# DP_Slave_Sch.net
KiCad netlist of a schematic drawn in Altium Designer
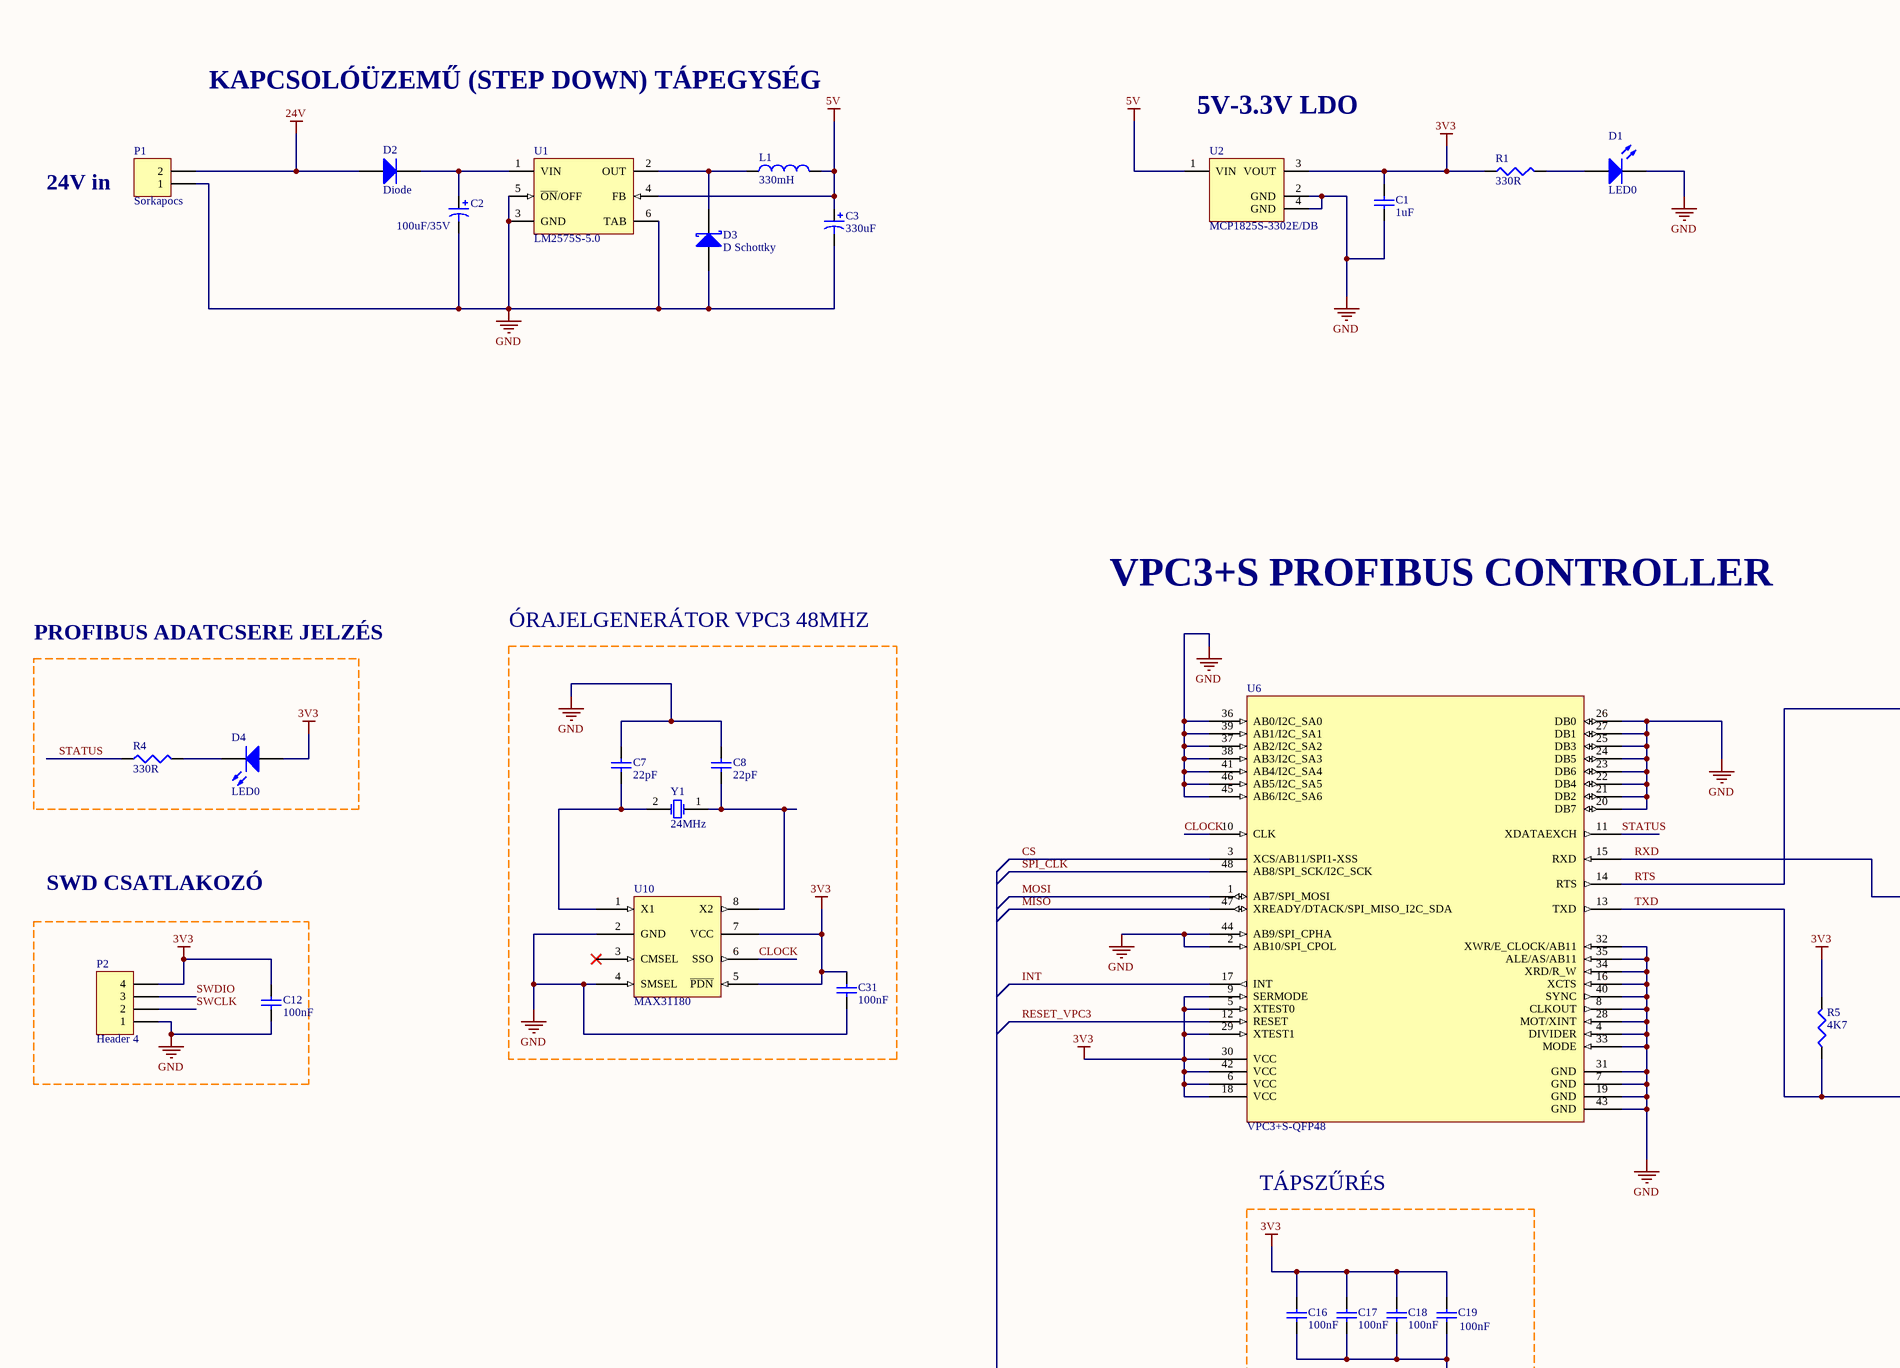
[diagram p0: DP_Slave_Sch.SchDoc, top left]
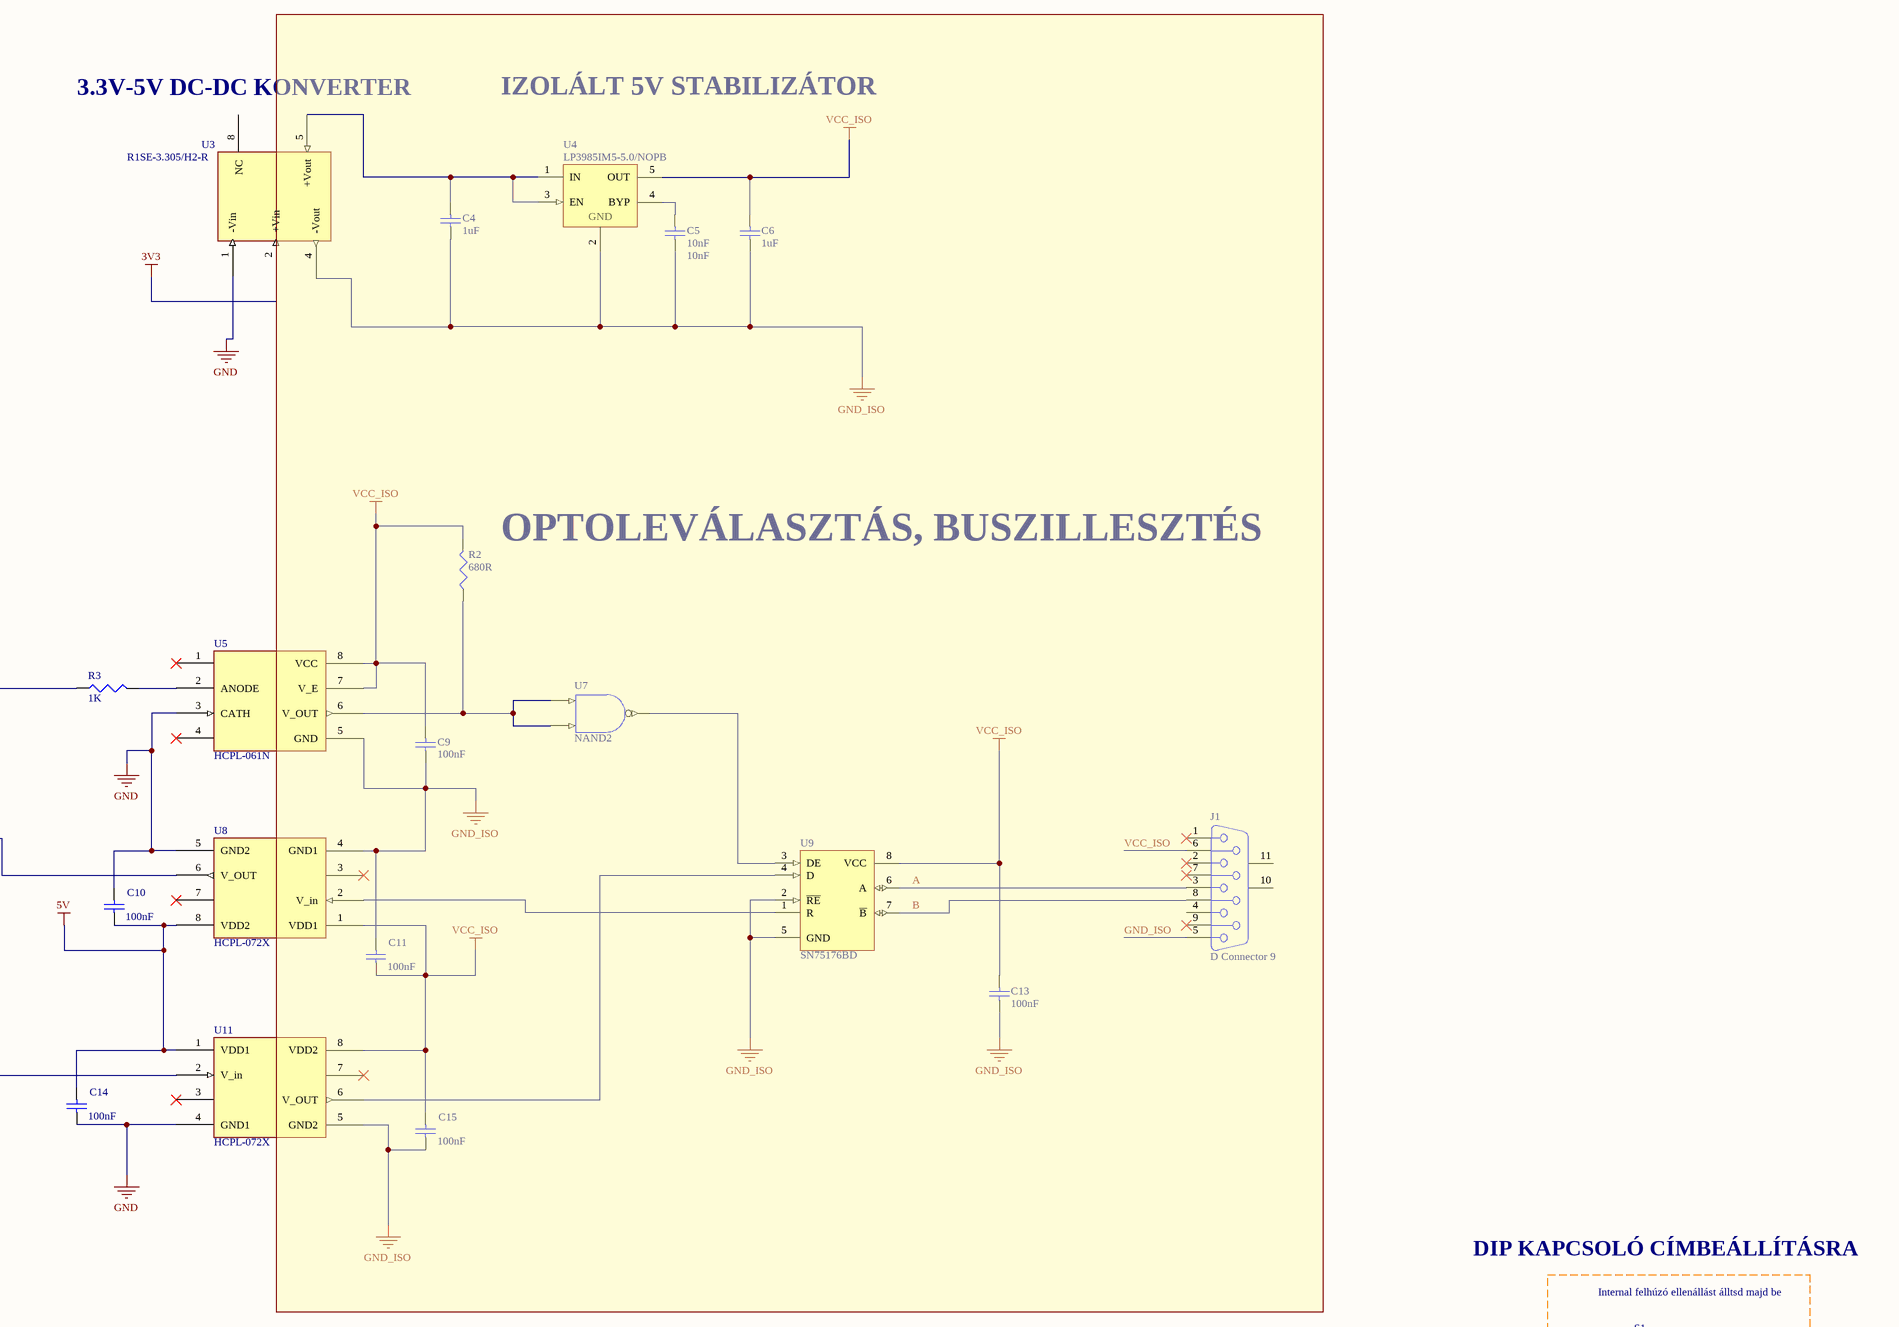
[diagram p1: DP_Slave_Sch.SchDoc, top right]
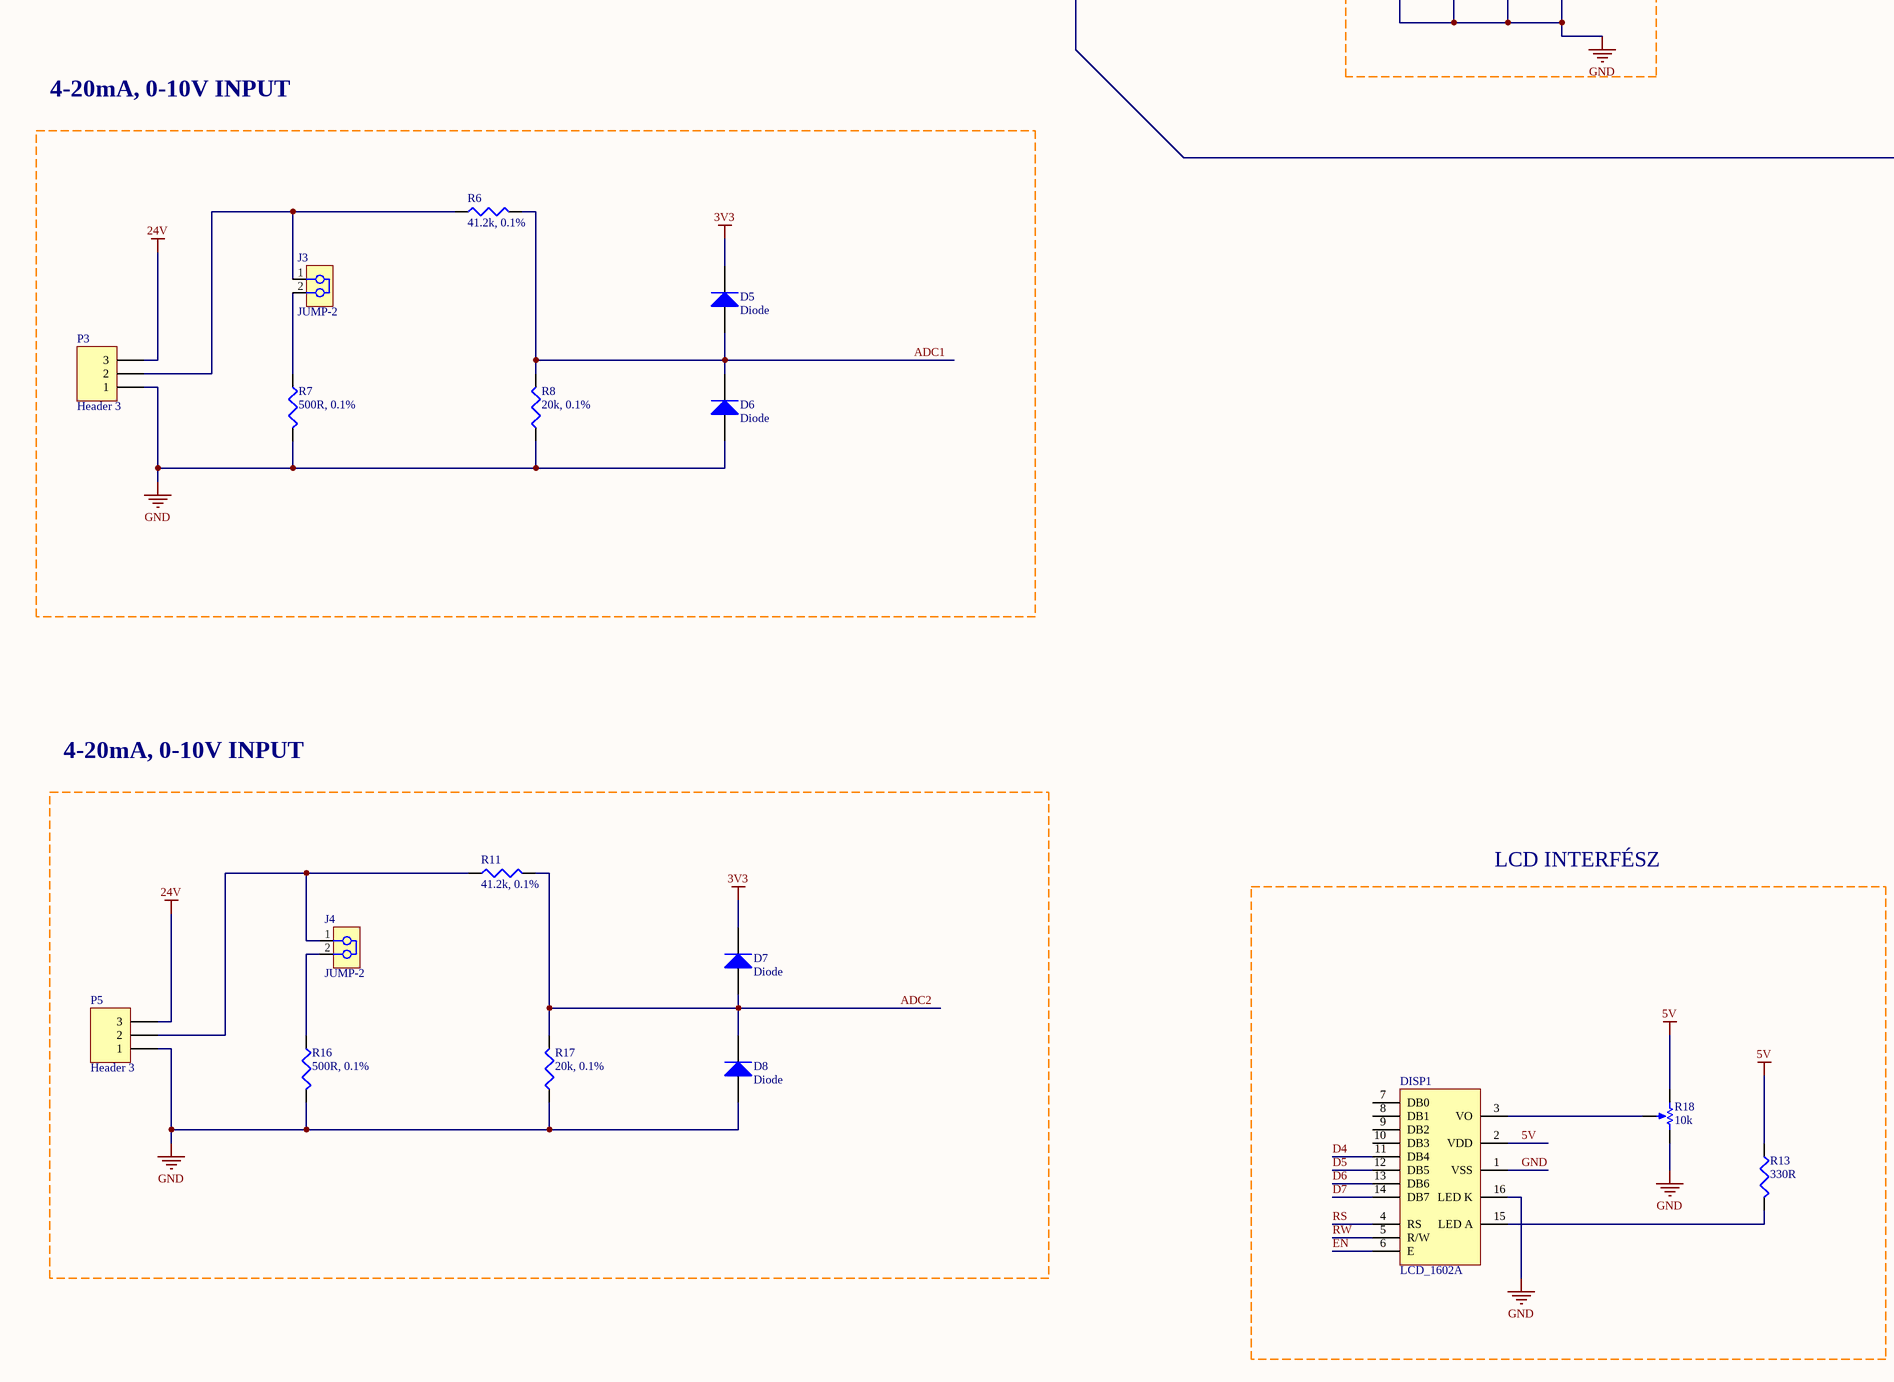
[diagram p2: DP_Slave_Sch.SchDoc, bottom left]
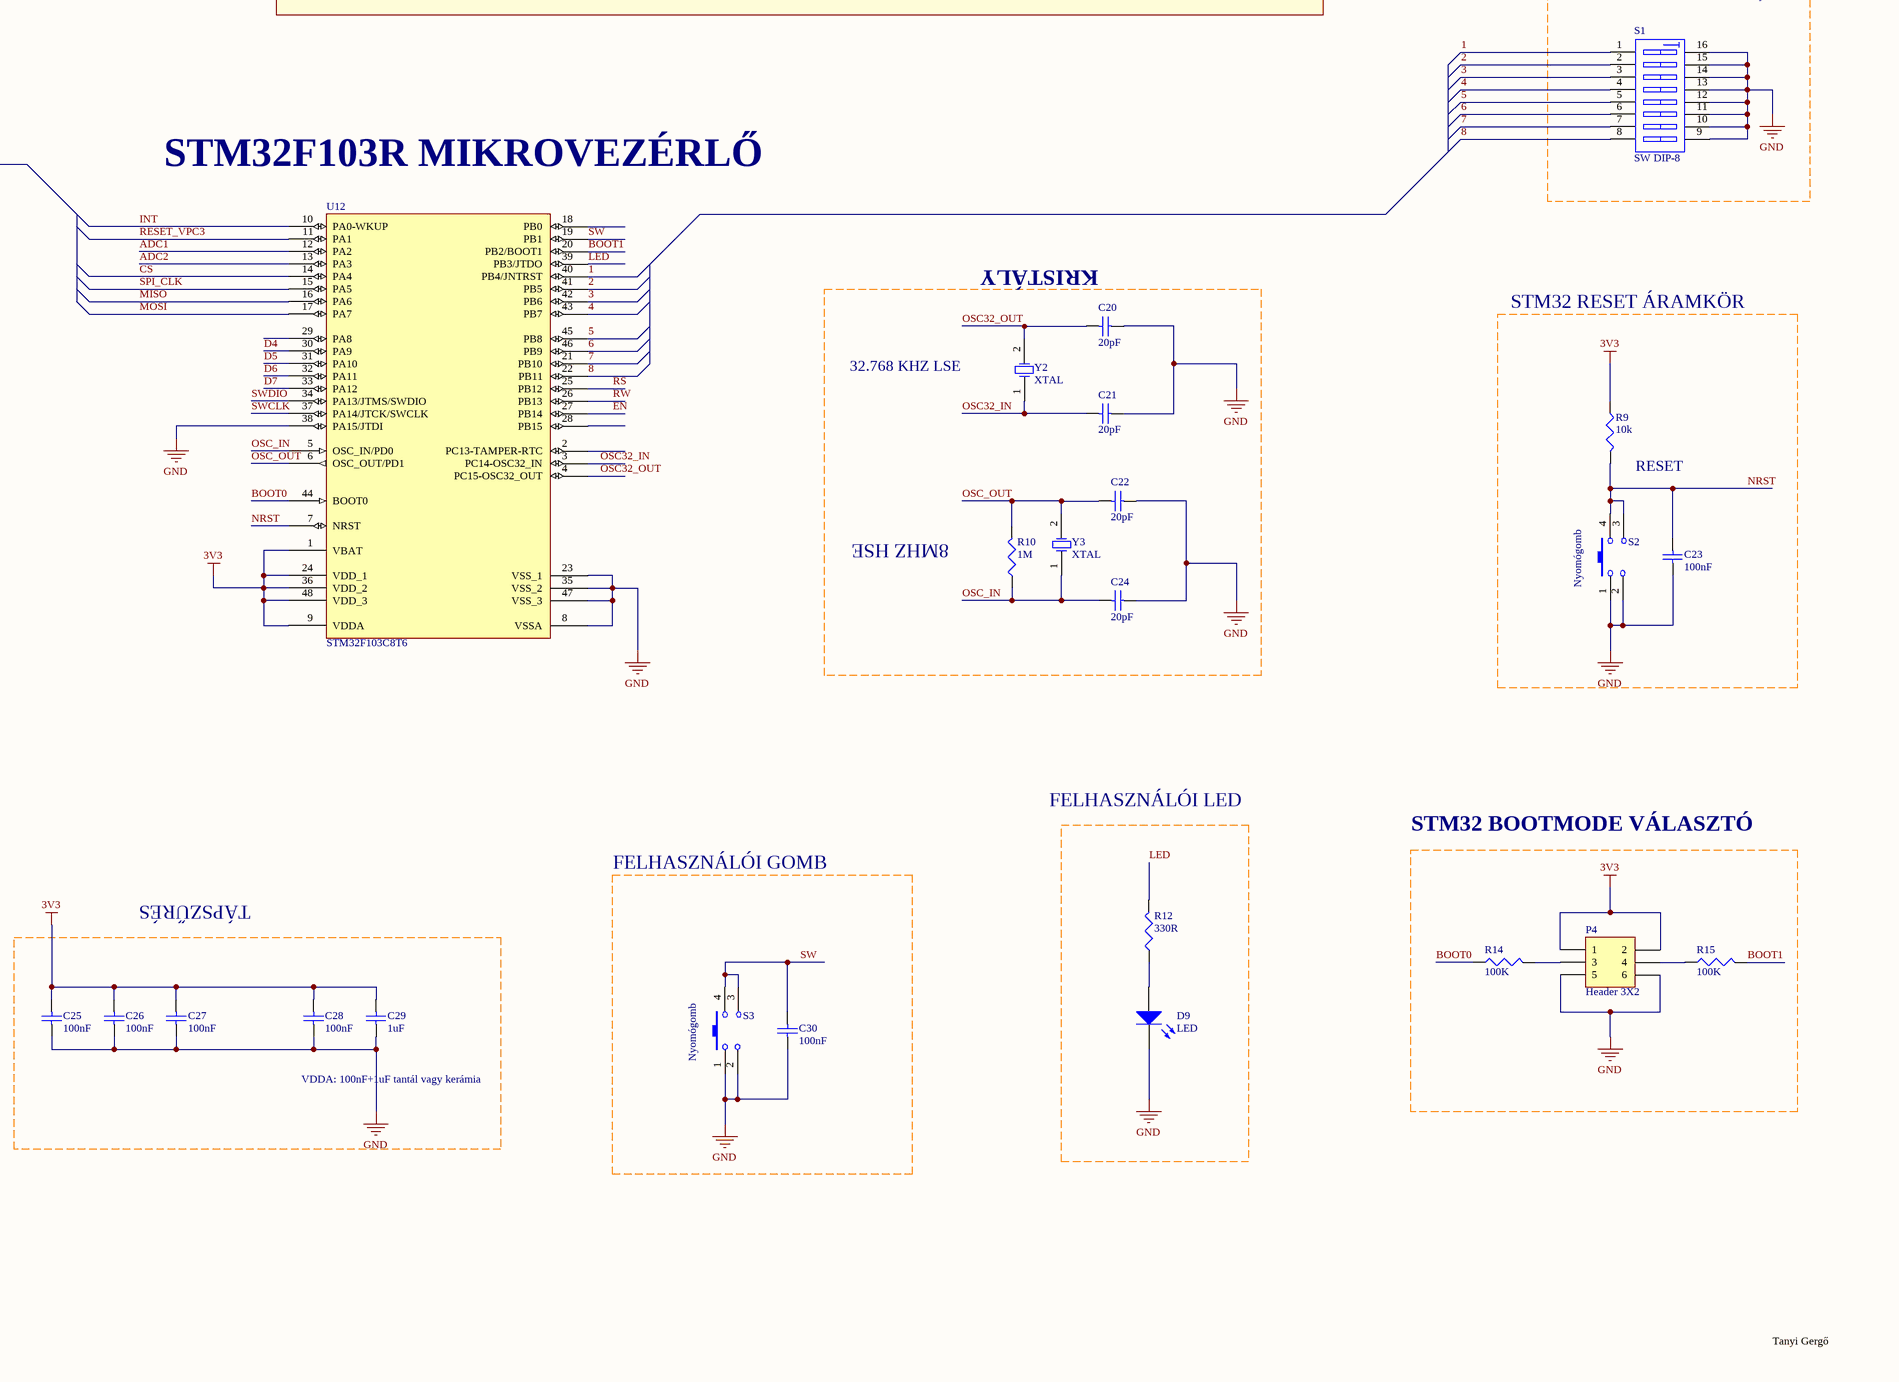
[diagram p3: DP_Slave_Sch.SchDoc, bottom right]

(export (version "E")
  (design (tool "Eeschema 10.0.6"))
  (components
    (comp (ref "C1")
      (value "1uF")
      (footprint "C1206")
      (description "Szűrőkondi")
      (fields (field (name "PUBLISHER") "Altium Limited"))
      (libsource (lib "Miscellaneous Devices") (part "Cap Semi"))
    )
    (comp (ref "C2")
      (value "100uF/35V")
      (footprint "MyFootprints:SMD Elkó")
      (description "SMD elkó/40V")
      (fields (field (name "PUBLISHER") "Altium Limited"))
      (libsource (lib "Miscellaneous Devices") (part "Cap Pol3"))
    )
    (comp (ref "C3")
      (value "330uF")
      (footprint "MyFootprints:SMD Elkó")
      (description "LDO kimeneti polárkondi")
      (fields (field (name "PUBLISHER") "Altium Limited"))
      (libsource (lib "Miscellaneous Devices") (part "Cap Pol3"))
    )
    (comp (ref "C4")
      (value "1uF")
      (footprint "C1206")
      (description "Capacitor (Semiconductor SIM Model)")
      (fields (field (name "PUBLISHER") "Altium Limited"))
      (libsource (lib "Miscellaneous Devices") (part "Cap Semi"))
    )
    (comp (ref "C5")
      (value "10nF")
      (footprint "C1206")
      (description "Capacitor (Semiconductor SIM Model)")
      (fields (field (name "ALTIUM_VALUE") "10nF") (field (name "PUBLISHER") "Altium Limited"))
      (libsource (lib "Miscellaneous Devices") (part "Cap Semi"))
    )
    (comp (ref "C6")
      (value "1uF")
      (footprint "C1206")
      (description "Capacitor (Semiconductor SIM Model)")
      (fields (field (name "PUBLISHER") "Altium Limited"))
      (libsource (lib "Miscellaneous Devices") (part "Cap Semi"))
    )
    (comp (ref "C7")
      (value "22pF")
      (footprint "C1206")
      (description "SMD kerámia")
      (fields (field (name "PUBLISHER") "Altium Limited"))
      (libsource (lib "Miscellaneous Devices") (part "Cap Semi"))
    )
    (comp (ref "C8")
      (value "22pF")
      (footprint "C1206")
      (description "SMD kerámia")
      (fields (field (name "PUBLISHER") "Altium Limited"))
      (libsource (lib "Miscellaneous Devices") (part "Cap Semi"))
    )
    (comp (ref "C9")
      (value "100nF")
      (footprint "C1206")
      (description "SMD KERÁMIA")
      (fields (field (name "PUBLISHER") "Altium Limited"))
      (libsource (lib "Miscellaneous Devices") (part "Cap Semi"))
    )
    (comp (ref "C10")
      (value "100nF")
      (footprint "C1206")
      (description "SMD KERÁMIA")
      (fields (field (name "PUBLISHER") "Altium Limited"))
      (libsource (lib "Miscellaneous Devices") (part "Cap Semi"))
    )
    (comp (ref "C11")
      (value "100nF")
      (footprint "C1206")
      (description "SMD KERÁMIA")
      (fields (field (name "PUBLISHER") "Altium Limited"))
      (libsource (lib "Miscellaneous Devices") (part "Cap Semi"))
    )
    (comp (ref "C12")
      (value "100nF")
      (footprint "C1206")
      (description "Szűrőkondi")
      (fields (field (name "PUBLISHER") "Altium Limited"))
      (libsource (lib "Miscellaneous Devices") (part "Cap Semi"))
    )
    (comp (ref "C13")
      (value "100nF")
      (footprint "C1206")
      (description "SMD KERÁMIA")
      (fields (field (name "PUBLISHER") "Altium Limited"))
      (libsource (lib "Miscellaneous Devices") (part "Cap Semi"))
    )
    (comp (ref "C14")
      (value "100nF")
      (footprint "C1206")
      (description "SMD KERÁMIA")
      (fields (field (name "PUBLISHER") "Altium Limited"))
      (libsource (lib "Miscellaneous Devices") (part "Cap Semi"))
    )
    (comp (ref "C15")
      (value "100nF")
      (footprint "C1206")
      (description "SMD KERÁMIA")
      (fields (field (name "PUBLISHER") "Altium Limited"))
      (libsource (lib "Miscellaneous Devices") (part "Cap Semi"))
    )
    (comp (ref "C16")
      (value "100nF")
      (footprint "C1206")
      (description "Capacitor (Semiconductor SIM Model)")
      (fields (field (name "PUBLISHER") "Altium Limited"))
      (libsource (lib "Miscellaneous Devices") (part "Cap Semi"))
    )
    (comp (ref "C17")
      (value "100nF")
      (footprint "C1206")
      (description "Capacitor (Semiconductor SIM Model)")
      (fields (field (name "PUBLISHER") "Altium Limited"))
      (libsource (lib "Miscellaneous Devices") (part "Cap Semi"))
    )
    (comp (ref "C18")
      (value "100nF")
      (footprint "C1206")
      (description "Capacitor (Semiconductor SIM Model)")
      (fields (field (name "PUBLISHER") "Altium Limited"))
      (libsource (lib "Miscellaneous Devices") (part "Cap Semi"))
    )
    (comp (ref "C19")
      (value "100nF")
      (footprint "C1206")
      (description "Capacitor (Semiconductor SIM Model)")
      (fields (field (name "PUBLISHER") "Altium Limited"))
      (libsource (lib "Miscellaneous Devices") (part "Cap Semi"))
    )
    (comp (ref "C20")
      (value "20pF")
      (footprint "C1206")
      (description "SMD kerámia")
      (fields (field (name "PUBLISHER") "Altium Limited"))
      (libsource (lib "Miscellaneous Devices") (part "Cap Semi"))
    )
    (comp (ref "C21")
      (value "20pF")
      (footprint "C1206")
      (description "SMD kerámia")
      (fields (field (name "PUBLISHER") "Altium Limited"))
      (libsource (lib "Miscellaneous Devices") (part "Cap Semi"))
    )
    (comp (ref "C22")
      (value "20pF")
      (footprint "C1206")
      (description "SMD kerámia")
      (fields (field (name "PUBLISHER") "Altium Limited"))
      (libsource (lib "Miscellaneous Devices") (part "Cap Semi"))
    )
    (comp (ref "C23")
      (value "100nF")
      (footprint "C1206")
      (description "Szűrőkondi")
      (fields (field (name "PUBLISHER") "Altium Limited"))
      (libsource (lib "Miscellaneous Devices") (part "Cap Semi"))
    )
    (comp (ref "C24")
      (value "20pF")
      (footprint "C1206")
      (description "SMD kerámia")
      (fields (field (name "PUBLISHER") "Altium Limited"))
      (libsource (lib "Miscellaneous Devices") (part "Cap Semi"))
    )
    (comp (ref "C25")
      (value "100nF")
      (footprint "C1206")
      (description "SMD kerámia")
      (fields (field (name "PUBLISHER") "Altium Limited"))
      (libsource (lib "Miscellaneous Devices") (part "Cap Semi"))
    )
    (comp (ref "C26")
      (value "100nF")
      (footprint "C1206")
      (description "SMD kerámia")
      (fields (field (name "PUBLISHER") "Altium Limited"))
      (libsource (lib "Miscellaneous Devices") (part "Cap Semi"))
    )
    (comp (ref "C27")
      (value "100nF")
      (footprint "C1206")
      (description "SMD kerámia")
      (fields (field (name "PUBLISHER") "Altium Limited"))
      (libsource (lib "Miscellaneous Devices") (part "Cap Semi"))
    )
    (comp (ref "C28")
      (value "100nF")
      (footprint "C1206")
      (description "SMD kerámia")
      (fields (field (name "PUBLISHER") "Altium Limited"))
      (libsource (lib "Miscellaneous Devices") (part "Cap Semi"))
    )
    (comp (ref "C29")
      (value "1uF")
      (footprint "C1206")
      (description "SMD kerámia")
      (fields (field (name "PUBLISHER") "Altium Limited"))
      (libsource (lib "Miscellaneous Devices") (part "Cap Semi"))
    )
    (comp (ref "C30")
      (value "100nF")
      (footprint "C1206")
      (description "SMD kerámia")
      (fields (field (name "PUBLISHER") "Altium Limited"))
      (libsource (lib "Miscellaneous Devices") (part "Cap Semi"))
    )
    (comp (ref "C31")
      (value "100nF")
      (footprint "C1206")
      (description "Capacitor (Semiconductor SIM Model)")
      (fields (field (name "PUBLISHER") "Altium Limited"))
      (libsource (lib "Miscellaneous Devices") (part "Cap Semi"))
    )
    (comp (ref "D1")
      (value "LED0")
      (footprint "C1206")
      (description "Typical INFRARED GaAs LED")
      (fields (field (name "PUBLISHER") "Altium Limited"))
      (libsource (lib "Miscellaneous Devices") (part "LED0"))
    )
    (comp (ref "D2")
      (value "Diode")
      (footprint "Dióda MiniMelf SOD80")
      (fields (field (name "PUBLISHER") "Altium Limited"))
      (libsource (lib "Miscellaneous Devices") (part "Diode"))
    )
    (comp (ref "D3")
      (value "D Schottky")
      (footprint "Tápegység_Teszt_Panel1:Schottky dióda")
      (description "Schottky Diode")
      (fields (field (name "PUBLISHER") "Altium Limited"))
      (libsource (lib "Miscellaneous Devices") (part "D Schottky"))
    )
    (comp (ref "D4")
      (value "LED0")
      (footprint "C1206")
      (description "Typical INFRARED GaAs LED")
      (fields (field (name "PUBLISHER") "Altium Limited"))
      (libsource (lib "Miscellaneous Devices") (part "LED0"))
    )
    (comp (ref "D5")
      (value "Diode")
      (footprint "Miscellaneous Devices:C1206")
      (description "Default Diode")
      (fields (field (name "PUBLISHER") "Altium Limited"))
      (libsource (lib "Miscellaneous Devices") (part "Diode"))
    )
    (comp (ref "D6")
      (value "Diode")
      (footprint "Miscellaneous Devices:C1206")
      (description "Default Diode")
      (fields (field (name "PUBLISHER") "Altium Limited"))
      (libsource (lib "Miscellaneous Devices") (part "Diode"))
    )
    (comp (ref "D7")
      (value "Diode")
      (footprint "Miscellaneous Devices:C1206")
      (description "Default Diode")
      (fields (field (name "PUBLISHER") "Altium Limited"))
      (libsource (lib "Miscellaneous Devices") (part "Diode"))
    )
    (comp (ref "D8")
      (value "Diode")
      (footprint "Miscellaneous Devices:C1206")
      (description "Default Diode")
      (fields (field (name "PUBLISHER") "Altium Limited"))
      (libsource (lib "Miscellaneous Devices") (part "Diode"))
    )
    (comp (ref "D9")
      (value "LED")
      (footprint "c1206")
      (description "Piros felhasználói LED")
      (fields (field (name "PUBLISHER") "Altium Limited"))
      (libsource (lib "Miscellaneous Devices") (part "LED2"))
    )
    (comp (ref "DISP1") (value "LCD_1602A") (footprint "LCD") (libsource (lib "Devices") (part "LCD_1602A")))
    (comp (ref "J1")
      (value "D Connector 9")
      (footprint "DSUB1.385-2H9")
      (description "Receptacle Assembly, 9 Position, Right Angle")
      (fields (field (name "PUBLISHER") "Altium Limited"))
      (libsource (lib "Miscellaneous Connectors") (part "D Connector 9"))
    )
    (comp (ref "J3") (value "JUMP-2") (footprint "HDR1X2") (libsource (lib "Devices") (part "JUMP-2")))
    (comp (ref "J4") (value "JUMP-2") (footprint "HDR1X2") (libsource (lib "Devices") (part "JUMP-2")))
    (comp (ref "L1")
      (value "330mH")
      (footprint "SMD tekercs")
      (description "Inductor")
      (fields (field (name "PUBLISHER") "Altium Limited"))
      (libsource (lib "Miscellaneous Devices") (part "Inductor"))
    )
    (comp (ref "P1")
      (value "Sorkapocs")
      (footprint "SORKAPOCS-2")
      (description "12V input")
      (fields (field (name "PUBLISHER") "Altium Limited"))
      (libsource (lib "Miscellaneous Connectors") (part "Header 2"))
    )
    (comp (ref "P2")
      (value "Header 4")
      (footprint "HDR1X4")
      (description "Header, 4-Pin")
      (fields (field (name "PUBLISHER") "Altium Limited"))
      (libsource (lib "Miscellaneous Connectors") (part "Header 4"))
    )
    (comp (ref "P3")
      (value "Header 3")
      (footprint "SORKAPOCS-3")
      (description "Header, 3-Pin")
      (fields (field (name "PUBLISHER") "Altium Limited"))
      (libsource (lib "Miscellaneous Connectors") (part "Header 3"))
    )
    (comp (ref "P4")
      (value "Header 3X2")
      (footprint "HDR2X3")
      (description "Header, 3-Pin, Dual row")
      (fields (field (name "PUBLISHER") "Altium Limited"))
      (libsource (lib "Miscellaneous Connectors") (part "Header 3X2"))
    )
    (comp (ref "P5")
      (value "Header 3")
      (footprint "SORKAPOCS-3")
      (description "Header, 3-Pin")
      (fields (field (name "PUBLISHER") "Altium Limited"))
      (libsource (lib "Miscellaneous Connectors") (part "Header 3"))
    )
    (comp (ref "R1")
      (value "330R")
      (footprint "Miscellaneous Devices:C1206")
      (description "SMD ellenállás")
      (fields (field (name "PUBLISHER") "Altium Limited"))
      (libsource (lib "Miscellaneous Devices") (part "Res3"))
    )
    (comp (ref "R2")
      (value "680R")
      (footprint "C1206")
      (description "Resistor")
      (fields (field (name "PUBLISHER") "Altium Limited"))
      (libsource (lib "Miscellaneous Devices") (part "Res3"))
    )
    (comp (ref "R3")
      (value "1K")
      (footprint "C1206")
      (description "SMD ELLENÁLLÁS")
      (fields (field (name "PUBLISHER") "Altium Limited"))
      (libsource (lib "Miscellaneous Devices") (part "Res3"))
    )
    (comp (ref "R4")
      (value "330R")
      (footprint "Miscellaneous Devices:C1206")
      (description "SMD ellenállás")
      (fields (field (name "PUBLISHER") "Altium Limited"))
      (libsource (lib "Miscellaneous Devices") (part "Res3"))
    )
    (comp (ref "R5")
      (value "4K7")
      (footprint "Miscellaneous Devices:C1206")
      (description "SMD ellenállás")
      (fields (field (name "PUBLISHER") "Altium Limited"))
      (libsource (lib "Miscellaneous Devices") (part "Res3"))
    )
    (comp (ref "R6")
      (value "41.2k, 0.1%")
      (footprint "C1206")
      (description "SMD ellenállás")
      (fields (field (name "PUBLISHER") "Altium Limited"))
      (libsource (lib "Miscellaneous Devices") (part "Res3"))
    )
    (comp (ref "R7")
      (value "500R, 0.1%")
      (footprint "C1206")
      (description "SMD ellenállás")
      (fields (field (name "PUBLISHER") "Altium Limited"))
      (libsource (lib "Miscellaneous Devices") (part "Res3"))
    )
    (comp (ref "R8")
      (value "20k, 0.1%")
      (footprint "C1206")
      (description "SMD ellenállás")
      (fields (field (name "PUBLISHER") "Altium Limited"))
      (libsource (lib "Miscellaneous Devices") (part "Res3"))
    )
    (comp (ref "R9")
      (value "10k")
      (footprint "C1206")
      (description "SMD ellenállás")
      (fields (field (name "PUBLISHER") "Altium Limited"))
      (libsource (lib "Miscellaneous Devices") (part "Res3"))
    )
    (comp (ref "R10")
      (value "1M")
      (footprint "c1206")
      (description "SMD ellenállás")
      (fields (field (name "PUBLISHER") "Altium Limited"))
      (libsource (lib "Miscellaneous Devices") (part "Res3"))
    )
    (comp (ref "R11")
      (value "41.2k, 0.1%")
      (footprint "C1206")
      (description "SMD ellenállás")
      (fields (field (name "PUBLISHER") "Altium Limited"))
      (libsource (lib "Miscellaneous Devices") (part "Res3"))
    )
    (comp (ref "R12")
      (value "330R")
      (footprint "c1206")
      (description "SMD ellenállás")
      (fields (field (name "PUBLISHER") "Altium Limited"))
      (libsource (lib "Miscellaneous Devices") (part "Res3"))
    )
    (comp (ref "R13")
      (value "330R")
      (footprint "C1206")
      (description "SMD ellenállás")
      (fields (field (name "PUBLISHER") "Altium Limited"))
      (libsource (lib "Miscellaneous Devices") (part "Res3"))
    )
    (comp (ref "R14")
      (value "100K")
      (footprint "Miscellaneous Devices:C1206")
      (description "SMD ellenállás")
      (fields (field (name "PUBLISHER") "Altium Limited"))
      (libsource (lib "Miscellaneous Devices") (part "Res3"))
    )
    (comp (ref "R15")
      (value "100K")
      (footprint "Miscellaneous Devices:C1206")
      (description "SMD ellenállás")
      (fields (field (name "PUBLISHER") "Altium Limited"))
      (libsource (lib "Miscellaneous Devices") (part "Res3"))
    )
    (comp (ref "R16")
      (value "500R, 0.1%")
      (footprint "C1206")
      (description "SMD ellenállás")
      (fields (field (name "PUBLISHER") "Altium Limited"))
      (libsource (lib "Miscellaneous Devices") (part "Res3"))
    )
    (comp (ref "R17")
      (value "20k, 0.1%")
      (footprint "C1206")
      (description "SMD ellenállás")
      (fields (field (name "PUBLISHER") "Altium Limited"))
      (libsource (lib "Miscellaneous Devices") (part "Res3"))
    )
    (comp (ref "R18")
      (value "10k")
      (footprint "Potméter")
      (description "Potentiometer")
      (fields (field (name "PUBLISHER") "Altium Limited"))
      (libsource (lib "Miscellaneous Devices") (part "RPot"))
    )
    (comp (ref "S1")
      (value "SW DIP-8")
      (footprint "MyFootprints:DIP switch")
      (description "DIP Switch, 8 Position, SPST")
      (fields (field (name "PUBLISHER") "Altium Limited"))
      (libsource (lib "Miscellaneous Devices") (part "SW DIP-8"))
    )
    (comp (ref "S2")
      (value "Nyomógomb")
      (footprint "Switch")
      (description "4 lábas, SMD, tactile")
      (libsource (lib "MyComponents") (part "Tactile switch"))
    )
    (comp (ref "S3")
      (value "Nyomógomb")
      (footprint "Switch")
      (description "4 lábas, SMD, tactile")
      (libsource (lib "MyComponents") (part "Tactile switch"))
    )
    (comp (ref "U1")
      (value "LM2575S-5.0")
      (footprint "NSC Audio:TS5B_N")
      (description "SIMPLE SWITCHER® 1A Step-Down Voltage Regulator, 5-pin TO-263")
      (fields
        (field (name "MANUFACTURER") "National Semiconductor")
        (field (name "PUBLISHER") "Altium Limited")
      )
      (libsource (lib "NSC Switcher") (part "LM2575S-5.0"))
    )
    (comp (ref "U2")
      (value "MCP1825S-3302E/DB")
      (footprint "Microchip Power Mgt Line Regulator:SOT-223-DB3_N")
      (description "500 mA, Low Voltage, Low Quiescent Current LDO Regulator, 3-Pin SOT-223, Extended Temperature")
      (fields (field (name "MANUFACTURER") "Microchip"))
      (libsource (lib "Microchip Power Management Line Regulator") (part "MCP1825S-3302E/DB"))
    )
    (comp (ref "U3")
      (value "R1SE-3.305/H2-R")
      (footprint "Isolated DC/DC converter")
      (description "Isolated DC/DC converter 3.3-5V")
      (libsource (lib "MyComponents") (part "R1SE-3.305/H2-R"))
    )
    (comp (ref "U4")
      (value "LP3985IM5-5.0/NOPB")
      (footprint "NSC LDO:MF05A_N")
      (description "Micropower, 150mA Low-Noise Ultra Low-Dropout CMOS Voltage Regulator, 5-pin SOT-23, Pb-Free")
      (fields
        (field (name "MANUFACTURER") "National Semiconductor")
        (field (name "PUBLISHER") "Altium Limited")
      )
      (libsource (lib "NSC LDO") (part "LP3985IM5-5.0/NOPB"))
    )
    (comp (ref "U5")
      (value "HCPL-061N")
      (footprint "HCPL-061N")
      (libsource (lib "Components") (part "HCPL-061N"))
    )
    (comp (ref "U6")
      (value "VPC3+S-QFP48")
      (footprint "TSQFP50P900X900X160-48N")
      (description "pROFIBUS CONTROLLER")
      (libsource (lib "MyComponents") (part "VPC3+S(1)"))
    )
    (comp (ref "U7")
      (value "NAND2")
      (footprint "MyFootprints:NAND gate DIP14")
      (description "2-Input NAND")
      (fields (field (name "PUBLISHER") "Altium Limited"))
      (libsource (lib "Actel Fusion FPGA") (part "NAND2"))
    )
    (comp (ref "U8")
      (value "HCPL-072X")
      (footprint "SOIC127P600X330-8N")
      (description "Optocoupler")
      (libsource (lib "Components") (part "HCPL-072X"))
    )
    (comp (ref "U9")
      (value "SN75176BD")
      (footprint "TI Interface Line Receiver:D008_L")
      (description "Differential Bus Transceiver")
      (fields (field (name "PUBLISHER") "Altium Limited"))
      (libsource (lib "TI Interface Line Transceiver") (part "SN75176BD"))
    )
    (comp (ref "U10")
      (value "MAX31180")
      (footprint "MAX31180AUA+ -  Clock Generator")
      (libsource (lib "MyComponents") (part "MAX31180"))
    )
    (comp (ref "U11")
      (value "HCPL-072X")
      (footprint "SOIC127P600X330-8N")
      (description "Optocoupler")
      (libsource (lib "") (part "HCPL-072X_1"))
    )
    (comp (ref "U12")
      (value "STM32F103C8T6")
      (footprint "ST Microcontroller 32-Bit STM32:LQFP48_N")
      (description "STM32 ARM-based 32-bit MCU with 64 Kbytes Flash, 48-pin LQFP, Industrial Temperature")
      (fields (field (name "PUBLISHER") "Altium Limited"))
      (libsource (lib "ST Microcontroller 32-Bit STM32") (part "STM32F103C8T6"))
    )
    (comp (ref "Y1")
      (value "24MHz")
      (footprint "8 MHz SMD kristály")
      (description "SMD kristály")
      (fields (field (name "PUBLISHER") "Altium Limited"))
      (libsource (lib "Miscellaneous Devices") (part "XTAL"))
    )
    (comp (ref "Y2")
      (value "XTAL")
      (footprint "MyFootprints:32.768 MHz SMD kristály")
      (description "32.768 KHz kristály")
      (fields (field (name "PUBLISHER") "Altium Limited"))
      (libsource (lib "Miscellaneous Devices") (part "XTAL"))
    )
    (comp (ref "Y3")
      (value "XTAL")
      (footprint "MyFootprints:8 MHz SMD kristály")
      (description "8 MHz kristály")
      (fields (field (name "PUBLISHER") "Altium Limited"))
      (libsource (lib "Miscellaneous Devices") (part "XTAL"))
    )
  )
  (nets
    (net (code "1") (name "/1") (class "Default")
      (node (ref "S1") (pin "1") (pinfunction "A1_1") (pintype "passive"))
      (node (ref "U12") (pin "40") (pinfunction "PB4/JNTRST_40") (pintype "bidirectional"))
    )
    (net (code "2") (name "/2") (class "Default")
      (node (ref "S1") (pin "2") (pinfunction "A2_2") (pintype "passive"))
      (node (ref "U12") (pin "41") (pinfunction "PB5_41") (pintype "bidirectional"))
    )
    (net (code "3") (name "/3") (class "Default")
      (node (ref "S1") (pin "3") (pinfunction "A3_3") (pintype "passive"))
      (node (ref "U12") (pin "42") (pinfunction "PB6_42") (pintype "bidirectional"))
    )
    (net (code "4") (name "/4") (class "Default")
      (node (ref "S1") (pin "4") (pinfunction "A4_4") (pintype "passive"))
      (node (ref "U12") (pin "43") (pinfunction "PB7_43") (pintype "bidirectional"))
    )
    (net (code "5") (name "/5") (class "Default")
      (node (ref "S1") (pin "5") (pinfunction "A5_5") (pintype "passive"))
      (node (ref "U12") (pin "45") (pinfunction "PB8_45") (pintype "bidirectional"))
    )
    (net (code "6") (name "/6") (class "Default")
      (node (ref "S1") (pin "6") (pinfunction "A6_6") (pintype "passive"))
      (node (ref "U12") (pin "46") (pinfunction "PB9_46") (pintype "bidirectional"))
    )
    (net (code "7") (name "/7") (class "Default")
      (node (ref "S1") (pin "7") (pinfunction "A7_7") (pintype "passive"))
      (node (ref "U12") (pin "21") (pinfunction "PB10_21") (pintype "bidirectional"))
    )
    (net (code "8") (name "/8") (class "Default")
      (node (ref "S1") (pin "8") (pinfunction "A8_8") (pintype "passive"))
      (node (ref "U12") (pin "22") (pinfunction "PB11_22") (pintype "bidirectional"))
    )
    (net (code "9") (name "/A") (class "Default")
      (node (ref "J1") (pin "3") (pinfunction "3_3") (pintype "passive"))
      (node (ref "U9") (pin "6") (pinfunction "A_6") (pintype "bidirectional"))
    )
    (net (code "10") (name "/ADC1") (class "Default")
      (node (ref "D5") (pin "1") (pinfunction "A_1") (pintype "passive"))
      (node (ref "D6") (pin "2") (pinfunction "K_2") (pintype "passive"))
      (node (ref "R6") (pin "2") (pinfunction "2_2") (pintype "passive"))
      (node (ref "R8") (pin "2") (pinfunction "2_2") (pintype "passive"))
      (node (ref "U12") (pin "12") (pinfunction "PA2_12") (pintype "bidirectional"))
    )
    (net (code "11") (name "/ADC2") (class "Default")
      (node (ref "D7") (pin "1") (pinfunction "A_1") (pintype "passive"))
      (node (ref "D8") (pin "2") (pinfunction "K_2") (pintype "passive"))
      (node (ref "R11") (pin "2") (pinfunction "2_2") (pintype "passive"))
      (node (ref "R17") (pin "2") (pinfunction "2_2") (pintype "passive"))
      (node (ref "U12") (pin "13") (pinfunction "PA3_13") (pintype "bidirectional"))
    )
    (net (code "12") (name "/B") (class "Default")
      (node (ref "J1") (pin "8") (pinfunction "8_8") (pintype "passive"))
      (node (ref "U9") (pin "7") (pinfunction "~{B}_7") (pintype "bidirectional"))
    )
    (net (code "13") (name "/BOOT0") (class "Default")
      (node (ref "R14") (pin "1") (pinfunction "1_1") (pintype "passive"))
      (node (ref "U12") (pin "44") (pinfunction "BOOT0_44") (pintype "input"))
    )
    (net (code "14") (name "/BOOT1") (class "Default")
      (node (ref "R15") (pin "2") (pinfunction "2_2") (pintype "passive"))
      (node (ref "U12") (pin "20") (pinfunction "PB2/BOOT1_20") (pintype "bidirectional"))
    )
    (net (code "15") (name "/CLOCK") (class "Default")
      (node (ref "U10") (pin "6") (pinfunction "SSO_6") (pintype "output"))
      (node (ref "U6") (pin "10") (pinfunction "CLK_10") (pintype "input"))
    )
    (net (code "16") (name "/CS") (class "Default")
      (node (ref "U12") (pin "14") (pinfunction "PA4_14") (pintype "bidirectional"))
      (node (ref "U6") (pin "3") (pinfunction "XCS/AB11/SPI1-XSS_3") (pintype "passive"))
    )
    (net (code "17") (name "/D4") (class "Default")
      (node (ref "DISP1") (pin "11") (pinfunction "DB4_11") (pintype "passive"))
      (node (ref "U12") (pin "30") (pinfunction "PA9_30") (pintype "bidirectional"))
    )
    (net (code "18") (name "/D5") (class "Default")
      (node (ref "DISP1") (pin "12") (pinfunction "DB5_12") (pintype "passive"))
      (node (ref "U12") (pin "31") (pinfunction "PA10_31") (pintype "bidirectional"))
    )
    (net (code "19") (name "/D6") (class "Default")
      (node (ref "DISP1") (pin "13") (pinfunction "DB6_13") (pintype "passive"))
      (node (ref "U12") (pin "32") (pinfunction "PA11_32") (pintype "bidirectional"))
    )
    (net (code "20") (name "/D7") (class "Default")
      (node (ref "DISP1") (pin "14") (pinfunction "DB7_14") (pintype "passive"))
      (node (ref "U12") (pin "33") (pinfunction "PA12_33") (pintype "bidirectional"))
    )
    (net (code "21") (name "/EN") (class "Default")
      (node (ref "DISP1") (pin "6") (pinfunction "E_6") (pintype "passive"))
      (node (ref "U12") (pin "27") (pinfunction "PB14_27") (pintype "bidirectional"))
    )
    (net (code "22") (name "/INT") (class "Default")
      (node (ref "U12") (pin "10") (pinfunction "PA0-WKUP_10") (pintype "bidirectional"))
      (node (ref "U6") (pin "17") (pinfunction "INT_17") (pintype "output"))
    )
    (net (code "23") (name "/LED") (class "Default")
      (node (ref "R12") (pin "2") (pinfunction "2_2") (pintype "passive"))
      (node (ref "U12") (pin "39") (pinfunction "PB3/JTDO_39") (pintype "bidirectional"))
    )
    (net (code "24") (name "/MISO") (class "Default")
      (node (ref "U12") (pin "16") (pinfunction "PA6_16") (pintype "bidirectional"))
      (node (ref "U6") (pin "47") (pinfunction "XREADY/DTACK/SPI_MISO_I2C_SDA_47") (pintype "bidirectional"))
    )
    (net (code "25") (name "/MOSI") (class "Default")
      (node (ref "U12") (pin "17") (pinfunction "PA7_17") (pintype "bidirectional"))
      (node (ref "U6") (pin "1") (pinfunction "AB7/SPI_MOSI_1") (pintype "bidirectional"))
    )
    (net (code "26") (name "/NRST") (class "Default")
      (node (ref "C23") (pin "2") (pinfunction "2_2") (pintype "passive"))
      (node (ref "R9") (pin "2") (pinfunction "2_2") (pintype "passive"))
      (node (ref "S2") (pin "3") (pinfunction "3_3") (pintype "passive"))
      (node (ref "S2") (pin "4") (pinfunction "4_4") (pintype "passive"))
      (node (ref "U12") (pin "7") (pinfunction "NRST_7") (pintype "bidirectional"))
    )
    (net (code "27") (name "/OSC32_IN") (class "Default")
      (node (ref "C21") (pin "2") (pinfunction "2_2") (pintype "passive"))
      (node (ref "U12") (pin "3") (pinfunction "PC14-OSC32_IN_3") (pintype "bidirectional"))
      (node (ref "Y2") (pin "1") (pinfunction "OSC1_1") (pintype "passive"))
    )
    (net (code "28") (name "/OSC32_OUT") (class "Default")
      (node (ref "C20") (pin "2") (pinfunction "2_2") (pintype "passive"))
      (node (ref "U12") (pin "4") (pinfunction "PC15-OSC32_OUT_4") (pintype "bidirectional"))
      (node (ref "Y2") (pin "2") (pinfunction "OSC2_2") (pintype "passive"))
    )
    (net (code "29") (name "/OSC_IN") (class "Default")
      (node (ref "C24") (pin "2") (pinfunction "2_2") (pintype "passive"))
      (node (ref "R10") (pin "1") (pinfunction "1_1") (pintype "passive"))
      (node (ref "U12") (pin "5") (pinfunction "OSC_IN/PD0_5") (pintype "input"))
      (node (ref "Y3") (pin "1") (pinfunction "OSC1_1") (pintype "passive"))
    )
    (net (code "30") (name "/OSC_OUT") (class "Default")
      (node (ref "C22") (pin "2") (pinfunction "2_2") (pintype "passive"))
      (node (ref "R10") (pin "2") (pinfunction "2_2") (pintype "passive"))
      (node (ref "U12") (pin "6") (pinfunction "OSC_OUT/PD1_6") (pintype "output"))
      (node (ref "Y3") (pin "2") (pinfunction "OSC2_2") (pintype "passive"))
    )
    (net (code "31") (name "/RESET_VPC3") (class "Default")
      (node (ref "U12") (pin "11") (pinfunction "PA1_11") (pintype "bidirectional"))
      (node (ref "U6") (pin "12") (pinfunction "RESET_12") (pintype "input"))
    )
    (net (code "32") (name "/RS") (class "Default")
      (node (ref "DISP1") (pin "4") (pinfunction "RS_4") (pintype "passive"))
      (node (ref "U12") (pin "25") (pinfunction "PB12_25") (pintype "bidirectional"))
    )
    (net (code "33") (name "/RTS") (class "Default")
      (node (ref "R3") (pin "1") (pinfunction "1_1") (pintype "passive"))
      (node (ref "U6") (pin "14") (pinfunction "RTS_14") (pintype "output"))
    )
    (net (code "34") (name "/RW") (class "Default")
      (node (ref "DISP1") (pin "5") (pinfunction "R/W_5") (pintype "passive"))
      (node (ref "U12") (pin "26") (pinfunction "PB13_26") (pintype "bidirectional"))
    )
    (net (code "35") (name "/RXD") (class "Default")
      (node (ref "U6") (pin "15") (pinfunction "RXD_15") (pintype "input"))
      (node (ref "U8") (pin "6") (pinfunction "V_OUT_6") (pintype "output"))
    )
    (net (code "36") (name "/SPI_CLK") (class "Default")
      (node (ref "U12") (pin "15") (pinfunction "PA5_15") (pintype "bidirectional"))
      (node (ref "U6") (pin "48") (pinfunction "AB8/SPI_SCK/I2C_SCK_48") (pintype "passive"))
    )
    (net (code "37") (name "/STATUS") (class "Default")
      (node (ref "R4") (pin "1") (pinfunction "1_1") (pintype "passive"))
      (node (ref "U6") (pin "11") (pinfunction "XDATAEXCH_11") (pintype "output"))
    )
    (net (code "38") (name "/SW") (class "Default")
      (node (ref "C30") (pin "2") (pinfunction "2_2") (pintype "passive"))
      (node (ref "S3") (pin "3") (pinfunction "3_3") (pintype "passive"))
      (node (ref "S3") (pin "4") (pinfunction "4_4") (pintype "passive"))
      (node (ref "U12") (pin "19") (pinfunction "PB1_19") (pintype "bidirectional"))
    )
    (net (code "39") (name "/SWCLK") (class "Default")
      (node (ref "P2") (pin "2") (pinfunction "2_2") (pintype "passive"))
      (node (ref "U12") (pin "37") (pinfunction "PA14/JTCK/SWCLK_37") (pintype "bidirectional"))
    )
    (net (code "40") (name "/SWDIO") (class "Default")
      (node (ref "P2") (pin "3") (pinfunction "3_3") (pintype "passive"))
      (node (ref "U12") (pin "34") (pinfunction "PA13/JTMS/SWDIO_34") (pintype "bidirectional"))
    )
    (net (code "41") (name "/TXD") (class "Default")
      (node (ref "R5") (pin "1") (pinfunction "1_1") (pintype "passive"))
      (node (ref "U11") (pin "2") (pinfunction "V_in_2") (pintype "input"))
      (node (ref "U6") (pin "13") (pinfunction "TXD_13") (pintype "output"))
    )
    (net (code "42") (name "3V3") (class "Default")
      (node (ref "C1") (pin "2") (pinfunction "2_2") (pintype "passive"))
      (node (ref "C12") (pin "2") (pinfunction "2_2") (pintype "passive"))
      (node (ref "C16") (pin "2") (pinfunction "2_2") (pintype "passive"))
      (node (ref "C17") (pin "2") (pinfunction "2_2") (pintype "passive"))
      (node (ref "C18") (pin "2") (pinfunction "2_2") (pintype "passive"))
      (node (ref "C19") (pin "2") (pinfunction "2_2") (pintype "passive"))
      (node (ref "C25") (pin "2") (pinfunction "2_2") (pintype "passive"))
      (node (ref "C26") (pin "2") (pinfunction "2_2") (pintype "passive"))
      (node (ref "C27") (pin "2") (pinfunction "2_2") (pintype "passive"))
      (node (ref "C28") (pin "2") (pinfunction "2_2") (pintype "passive"))
      (node (ref "C29") (pin "2") (pinfunction "2_2") (pintype "passive"))
      (node (ref "C31") (pin "2") (pinfunction "2_2") (pintype "passive"))
      (node (ref "D4") (pin "1") (pinfunction "A_1") (pintype "passive"))
      (node (ref "D5") (pin "2") (pinfunction "K_2") (pintype "passive"))
      (node (ref "D7") (pin "2") (pinfunction "K_2") (pintype "passive"))
      (node (ref "P2") (pin "4") (pinfunction "4_4") (pintype "passive"))
      (node (ref "P4") (pin "1") (pinfunction "1_1") (pintype "passive"))
      (node (ref "P4") (pin "2") (pinfunction "2_2") (pintype "passive"))
      (node (ref "R1") (pin "1") (pinfunction "1_1") (pintype "passive"))
      (node (ref "R5") (pin "2") (pinfunction "2_2") (pintype "passive"))
      (node (ref "R9") (pin "1") (pinfunction "1_1") (pintype "passive"))
      (node (ref "U10") (pin "5") (pinfunction "~{PDN}_5") (pintype "input"))
      (node (ref "U10") (pin "7") (pinfunction "VCC_7") (pintype "power_in"))
      (node (ref "U12") (pin "1") (pinfunction "VBAT_1") (pintype "power_in"))
      (node (ref "U12") (pin "24") (pinfunction "VDD_1_24") (pintype "power_in"))
      (node (ref "U12") (pin "36") (pinfunction "VDD_2_36") (pintype "power_in"))
      (node (ref "U12") (pin "48") (pinfunction "VDD_3_48") (pintype "power_in"))
      (node (ref "U12") (pin "9") (pinfunction "VDDA_9") (pintype "power_in"))
      (node (ref "U2") (pin "3") (pinfunction "VOUT_3") (pintype "power_in"))
      (node (ref "U3") (pin "2") (pinfunction "+Vin_2") (pintype "input"))
      (node (ref "U6") (pin "18") (pinfunction "VCC_18") (pintype "power_in"))
      (node (ref "U6") (pin "29") (pinfunction "XTEST1_29") (pintype "input"))
      (node (ref "U6") (pin "30") (pinfunction "VCC_30") (pintype "power_in"))
      (node (ref "U6") (pin "42") (pinfunction "VCC_42") (pintype "power_in"))
      (node (ref "U6") (pin "5") (pinfunction "XTEST0_5") (pintype "input"))
      (node (ref "U6") (pin "6") (pinfunction "VCC_6") (pintype "power_in"))
      (node (ref "U6") (pin "9") (pinfunction "SERMODE_9") (pintype "input"))
    )
    (net (code "43") (name "5V") (class "Default")
      (node (ref "C10") (pin "1") (pinfunction "1_1") (pintype "passive"))
      (node (ref "C14") (pin "2") (pinfunction "2_2") (pintype "passive"))
      (node (ref "C3") (pin "1") (pinfunction "1_1") (pintype "passive"))
      (node (ref "DISP1") (pin "2") (pinfunction "VDD_2") (pintype "passive"))
      (node (ref "L1") (pin "2") (pinfunction "2_2") (pintype "passive"))
      (node (ref "R13") (pin "1") (pinfunction "1_1") (pintype "passive"))
      (node (ref "R18") (pin "1") (pinfunction "TOP_1") (pintype "passive"))
      (node (ref "U1") (pin "4") (pinfunction "FB_4") (pintype "input"))
      (node (ref "U11") (pin "1") (pinfunction "VDD1_1") (pintype "power_in"))
      (node (ref "U2") (pin "1") (pinfunction "VIN_1") (pintype "power_in"))
      (node (ref "U8") (pin "8") (pinfunction "VDD2_8") (pintype "power_in"))
    )
    (net (code "44") (name "24V") (class "Default")
      (node (ref "D2") (pin "1") (pinfunction "A_1") (pintype "passive"))
      (node (ref "P1") (pin "2") (pinfunction "2_2") (pintype "passive"))
      (node (ref "P3") (pin "3") (pinfunction "3_3") (pintype "passive"))
      (node (ref "P5") (pin "3") (pinfunction "3_3") (pintype "passive"))
    )
    (net (code "45") (name "GND") (class "Default")
      (node (ref "C1") (pin "1") (pinfunction "1_1") (pintype "passive"))
      (node (ref "C10") (pin "2") (pinfunction "2_2") (pintype "passive"))
      (node (ref "C12") (pin "1") (pinfunction "1_1") (pintype "passive"))
      (node (ref "C14") (pin "1") (pinfunction "1_1") (pintype "passive"))
      (node (ref "C16") (pin "1") (pinfunction "1_1") (pintype "passive"))
      (node (ref "C17") (pin "1") (pinfunction "1_1") (pintype "passive"))
      (node (ref "C18") (pin "1") (pinfunction "1_1") (pintype "passive"))
      (node (ref "C19") (pin "1") (pinfunction "1_1") (pintype "passive"))
      (node (ref "C2") (pin "2") (pinfunction "2_2") (pintype "passive"))
      (node (ref "C20") (pin "1") (pinfunction "1_1") (pintype "passive"))
      (node (ref "C21") (pin "1") (pinfunction "1_1") (pintype "passive"))
      (node (ref "C22") (pin "1") (pinfunction "1_1") (pintype "passive"))
      (node (ref "C23") (pin "1") (pinfunction "1_1") (pintype "passive"))
      (node (ref "C24") (pin "1") (pinfunction "1_1") (pintype "passive"))
      (node (ref "C25") (pin "1") (pinfunction "1_1") (pintype "passive"))
      (node (ref "C26") (pin "1") (pinfunction "1_1") (pintype "passive"))
      (node (ref "C27") (pin "1") (pinfunction "1_1") (pintype "passive"))
      (node (ref "C28") (pin "1") (pinfunction "1_1") (pintype "passive"))
      (node (ref "C29") (pin "1") (pinfunction "1_1") (pintype "passive"))
      (node (ref "C3") (pin "2") (pinfunction "2_2") (pintype "passive"))
      (node (ref "C30") (pin "1") (pinfunction "1_1") (pintype "passive"))
      (node (ref "C31") (pin "1") (pinfunction "1_1") (pintype "passive"))
      (node (ref "C7") (pin "2") (pinfunction "2_2") (pintype "passive"))
      (node (ref "C8") (pin "2") (pinfunction "2_2") (pintype "passive"))
      (node (ref "D1") (pin "2") (pinfunction "K_2") (pintype "passive"))
      (node (ref "D3") (pin "1") (pinfunction "A_1") (pintype "passive"))
      (node (ref "D6") (pin "1") (pinfunction "A_1") (pintype "passive"))
      (node (ref "D8") (pin "1") (pinfunction "A_1") (pintype "passive"))
      (node (ref "D9") (pin "2") (pinfunction "K_2") (pintype "passive"))
      (node (ref "DISP1") (pin "1") (pinfunction "VSS_1") (pintype "passive"))
      (node (ref "DISP1") (pin "16") (pinfunction "LED_K_16") (pintype "passive"))
      (node (ref "P1") (pin "1") (pinfunction "1_1") (pintype "passive"))
      (node (ref "P2") (pin "1") (pinfunction "1_1") (pintype "passive"))
      (node (ref "P3") (pin "1") (pinfunction "1_1") (pintype "passive"))
      (node (ref "P4") (pin "5") (pinfunction "5_5") (pintype "passive"))
      (node (ref "P4") (pin "6") (pinfunction "6_6") (pintype "passive"))
      (node (ref "P5") (pin "1") (pinfunction "1_1") (pintype "passive"))
      (node (ref "R16") (pin "2") (pinfunction "2_2") (pintype "passive"))
      (node (ref "R17") (pin "1") (pinfunction "1_1") (pintype "passive"))
      (node (ref "R18") (pin "2") (pinfunction "BOT_2") (pintype "passive"))
      (node (ref "R7") (pin "2") (pinfunction "2_2") (pintype "passive"))
      (node (ref "R8") (pin "1") (pinfunction "1_1") (pintype "passive"))
      (node (ref "S1") (pin "10") (pinfunction "B7_10") (pintype "passive"))
      (node (ref "S1") (pin "11") (pinfunction "B6_11") (pintype "passive"))
      (node (ref "S1") (pin "12") (pinfunction "B5_12") (pintype "passive"))
      (node (ref "S1") (pin "13") (pinfunction "B4_13") (pintype "passive"))
      (node (ref "S1") (pin "14") (pinfunction "B3_14") (pintype "passive"))
      (node (ref "S1") (pin "15") (pinfunction "B2_15") (pintype "passive"))
      (node (ref "S1") (pin "16") (pinfunction "B1_16") (pintype "passive"))
      (node (ref "S1") (pin "9") (pinfunction "B8_9") (pintype "passive"))
      (node (ref "S2") (pin "1") (pinfunction "1_1") (pintype "passive"))
      (node (ref "S2") (pin "2") (pinfunction "2_2") (pintype "passive"))
      (node (ref "S3") (pin "1") (pinfunction "1_1") (pintype "passive"))
      (node (ref "S3") (pin "2") (pinfunction "2_2") (pintype "passive"))
      (node (ref "U1") (pin "3") (pinfunction "GND_3") (pintype "power_in"))
      (node (ref "U1") (pin "5") (pinfunction "~{ON}/OFF_5") (pintype "input"))
      (node (ref "U1") (pin "6") (pinfunction "TAB_6") (pintype "power_in"))
      (node (ref "U10") (pin "2") (pinfunction "GND_2") (pintype "passive"))
      (node (ref "U10") (pin "4") (pinfunction "SMSEL_4") (pintype "input"))
      (node (ref "U11") (pin "4") (pinfunction "GND1_4") (pintype "power_in"))
      (node (ref "U12") (pin "23") (pinfunction "VSS_1_23") (pintype "power_in"))
      (node (ref "U12") (pin "35") (pinfunction "VSS_2_35") (pintype "power_in"))
      (node (ref "U12") (pin "38") (pinfunction "PA15/JTDI_38") (pintype "bidirectional"))
      (node (ref "U12") (pin "47") (pinfunction "VSS_3_47") (pintype "power_in"))
      (node (ref "U12") (pin "8") (pinfunction "VSSA_8") (pintype "power_in"))
      (node (ref "U2") (pin "2") (pinfunction "GND_2") (pintype "power_in"))
      (node (ref "U2") (pin "4") (pinfunction "GND_4") (pintype "power_in"))
      (node (ref "U3") (pin "1") (pinfunction "-Vin_1") (pintype "input"))
      (node (ref "U5") (pin "3") (pinfunction "CATH_3") (pintype "input"))
      (node (ref "U6") (pin "16") (pinfunction "XCTS_16") (pintype "input"))
      (node (ref "U6") (pin "19") (pinfunction "GND_19") (pintype "passive"))
      (node (ref "U6") (pin "2") (pinfunction "AB10/SPI_CPOL_2") (pintype "input"))
      (node (ref "U6") (pin "20") (pinfunction "DB7_20") (pintype "bidirectional"))
      (node (ref "U6") (pin "21") (pinfunction "DB2_21") (pintype "bidirectional"))
      (node (ref "U6") (pin "22") (pinfunction "DB4_22") (pintype "bidirectional"))
      (node (ref "U6") (pin "23") (pinfunction "DB6_23") (pintype "bidirectional"))
      (node (ref "U6") (pin "24") (pinfunction "DB5_24") (pintype "bidirectional"))
      (node (ref "U6") (pin "25") (pinfunction "DB3_25") (pintype "bidirectional"))
      (node (ref "U6") (pin "26") (pinfunction "DB0_26") (pintype "bidirectional"))
      (node (ref "U6") (pin "27") (pinfunction "DB1_27") (pintype "bidirectional"))
      (node (ref "U6") (pin "28") (pinfunction "MOT/XINT_28") (pintype "input"))
      (node (ref "U6") (pin "31") (pinfunction "GND_31") (pintype "passive"))
      (node (ref "U6") (pin "32") (pinfunction "XWR/E_CLOCK/AB11_32") (pintype "input"))
      (node (ref "U6") (pin "33") (pinfunction "MODE_33") (pintype "input"))
      (node (ref "U6") (pin "34") (pinfunction "XRD/R_W_34") (pintype "input"))
      (node (ref "U6") (pin "35") (pinfunction "ALE/AS/AB11_35") (pintype "input"))
      (node (ref "U6") (pin "36") (pinfunction "AB0/I2C_SA0_36") (pintype "input"))
      (node (ref "U6") (pin "37") (pinfunction "AB2/I2C_SA2_37") (pintype "input"))
      (node (ref "U6") (pin "38") (pinfunction "AB3/I2C_SA3_38") (pintype "input"))
      (node (ref "U6") (pin "39") (pinfunction "AB1/I2C_SA1_39") (pintype "input"))
      (node (ref "U6") (pin "4") (pinfunction "DIVIDER_4") (pintype "input"))
      (node (ref "U6") (pin "40") (pinfunction "SYNC_40") (pintype "output"))
      (node (ref "U6") (pin "41") (pinfunction "AB4/I2C_SA4_41") (pintype "input"))
      (node (ref "U6") (pin "43") (pinfunction "GND_43") (pintype "passive"))
      (node (ref "U6") (pin "44") (pinfunction "AB9/SPI_CPHA_44") (pintype "input"))
      (node (ref "U6") (pin "45") (pinfunction "AB6/I2C_SA6_45") (pintype "input"))
      (node (ref "U6") (pin "46") (pinfunction "AB5/I2C_SA5_46") (pintype "input"))
      (node (ref "U6") (pin "7") (pinfunction "GND_7") (pintype "passive"))
      (node (ref "U6") (pin "8") (pinfunction "CLKOUT_8") (pintype "output"))
      (node (ref "U8") (pin "5") (pinfunction "GND2_5") (pintype "power_in"))
    )
    (net (code "46") (name "GND_ISO") (class "Default")
      (node (ref "C11") (pin "2") (pinfunction "2_2") (pintype "passive"))
      (node (ref "C13") (pin "1") (pinfunction "1_1") (pintype "passive"))
      (node (ref "C15") (pin "1") (pinfunction "1_1") (pintype "passive"))
      (node (ref "C4") (pin "1") (pinfunction "1_1") (pintype "passive"))
      (node (ref "C5") (pin "1") (pinfunction "1_1") (pintype "passive"))
      (node (ref "C6") (pin "1") (pinfunction "1_1") (pintype "passive"))
      (node (ref "C9") (pin "1") (pinfunction "1_1") (pintype "passive"))
      (node (ref "J1") (pin "5") (pinfunction "5_5") (pintype "passive"))
      (node (ref "U11") (pin "5") (pinfunction "GND2_5") (pintype "power_in"))
      (node (ref "U3") (pin "4") (pinfunction "-Vout_4") (pintype "output"))
      (node (ref "U4") (pin "2") (pinfunction "GND_2") (pintype "power_in"))
      (node (ref "U5") (pin "5") (pinfunction "GND_5") (pintype "power_in"))
      (node (ref "U8") (pin "4") (pinfunction "GND1_4") (pintype "power_in"))
      (node (ref "U9") (pin "2") (pinfunction "~{RE}_2") (pintype "input"))
      (node (ref "U9") (pin "5") (pinfunction "GND_5") (pintype "power_in"))
    )
    (net (code "47") (name "Net-(D1-A)") (class "Default")
      (node (ref "D1") (pin "1") (pinfunction "A_1") (pintype "passive"))
      (node (ref "R1") (pin "2") (pinfunction "2_2") (pintype "passive"))
    )
    (net (code "48") (name "Net-(D2-K)") (class "Default")
      (node (ref "C2") (pin "1") (pinfunction "1_1") (pintype "passive"))
      (node (ref "D2") (pin "2") (pinfunction "K_2") (pintype "passive"))
      (node (ref "U1") (pin "1") (pinfunction "VIN_1") (pintype "power_in"))
    )
    (net (code "49") (name "Net-(D3-K)") (class "Default")
      (node (ref "D3") (pin "2") (pinfunction "K_2") (pintype "passive"))
      (node (ref "L1") (pin "1") (pinfunction "1_1") (pintype "passive"))
      (node (ref "U1") (pin "2") (pinfunction "OUT_2") (pintype "power_in"))
    )
    (net (code "50") (name "Net-(D4-K)") (class "Default")
      (node (ref "D4") (pin "2") (pinfunction "K_2") (pintype "passive"))
      (node (ref "R4") (pin "2") (pinfunction "2_2") (pintype "passive"))
    )
    (net (code "51") (name "Net-(D9-A)") (class "Default")
      (node (ref "D9") (pin "1") (pinfunction "A_1") (pintype "passive"))
      (node (ref "R12") (pin "1") (pinfunction "1_1") (pintype "passive"))
    )
    (net (code "52") (name "Net-(DISP1-LED_A)") (class "Default")
      (node (ref "DISP1") (pin "15") (pinfunction "LED_A_15") (pintype "passive"))
      (node (ref "R13") (pin "2") (pinfunction "2_2") (pintype "passive"))
    )
    (net (code "53") (name "Net-(DISP1-VO)") (class "Default")
      (node (ref "DISP1") (pin "3") (pinfunction "VO_3") (pintype "passive"))
      (node (ref "R18") (pin "3") (pinfunction "TAP_3") (pintype "passive"))
    )
    (net (code "54") (name "Net-(J3-C1)") (class "Default")
      (node (ref "J3") (pin "1") (pinfunction "C1_1") (pintype "passive"))
      (node (ref "P3") (pin "2") (pinfunction "2_2") (pintype "passive"))
      (node (ref "R6") (pin "1") (pinfunction "1_1") (pintype "passive"))
    )
    (net (code "55") (name "Net-(J3-C2)") (class "Default")
      (node (ref "J3") (pin "2") (pinfunction "C2_2") (pintype "passive"))
      (node (ref "R7") (pin "1") (pinfunction "1_1") (pintype "passive"))
    )
    (net (code "56") (name "Net-(J4-C1)") (class "Default")
      (node (ref "J4") (pin "1") (pinfunction "C1_1") (pintype "passive"))
      (node (ref "P5") (pin "2") (pinfunction "2_2") (pintype "passive"))
      (node (ref "R11") (pin "1") (pinfunction "1_1") (pintype "passive"))
    )
    (net (code "57") (name "Net-(J4-C2)") (class "Default")
      (node (ref "J4") (pin "2") (pinfunction "C2_2") (pintype "passive"))
      (node (ref "R16") (pin "1") (pinfunction "1_1") (pintype "passive"))
    )
    (net (code "58") (name "Net-(P4-Pad3)") (class "Default")
      (node (ref "P4") (pin "3") (pinfunction "3_3") (pintype "passive"))
      (node (ref "R14") (pin "2") (pinfunction "2_2") (pintype "passive"))
    )
    (net (code "59") (name "Net-(P4-Pad4)") (class "Default")
      (node (ref "P4") (pin "4") (pinfunction "4_4") (pintype "passive"))
      (node (ref "R15") (pin "1") (pinfunction "1_1") (pintype "passive"))
    )
    (net (code "60") (name "Net-(U3-+Vout)") (class "Default")
      (node (ref "C4") (pin "2") (pinfunction "2_2") (pintype "passive"))
      (node (ref "U3") (pin "5") (pinfunction "+Vout_5") (pintype "input"))
      (node (ref "U4") (pin "1") (pinfunction "IN_1") (pintype "power_in"))
      (node (ref "U4") (pin "3") (pinfunction "EN_3") (pintype "input"))
    )
    (net (code "61") (name "Net-(U4-BYP)") (class "Default")
      (node (ref "C5") (pin "2") (pinfunction "2_2") (pintype "passive"))
      (node (ref "U4") (pin "4") (pinfunction "BYP_4") (pintype "passive"))
    )
    (net (code "62") (name "Net-(U5-ANODE)") (class "Default")
      (node (ref "R3") (pin "2") (pinfunction "2_2") (pintype "passive"))
      (node (ref "U5") (pin "2") (pinfunction "ANODE_2") (pintype "power_in"))
    )
    (net (code "63") (name "Net-(U5-V_OUT)") (class "Default")
      (node (ref "R2") (pin "1") (pinfunction "1_1") (pintype "passive"))
      (node (ref "U5") (pin "6") (pinfunction "V_OUT_6") (pintype "output"))
      (node (ref "U7") (pin "1") (pinfunction "A_1") (pintype "input"))
      (node (ref "U7") (pin "2") (pinfunction "B_2") (pintype "input"))
    )
    (net (code "64") (name "Net-(U7-Y)") (class "Default")
      (node (ref "U7") (pin "3") (pinfunction "Y_3") (pintype "output"))
      (node (ref "U9") (pin "3") (pinfunction "DE_3") (pintype "input"))
    )
    (net (code "65") (name "Net-(U8-V_in)") (class "Default")
      (node (ref "U8") (pin "2") (pinfunction "V_in_2") (pintype "input"))
      (node (ref "U9") (pin "1") (pinfunction "R_1") (pintype "tri_state"))
    )
    (net (code "66") (name "Net-(U10-X1)") (class "Default")
      (node (ref "C7") (pin "1") (pinfunction "1_1") (pintype "passive"))
      (node (ref "U10") (pin "1") (pinfunction "X1_1") (pintype "input"))
      (node (ref "Y1") (pin "2") (pinfunction "OSC2_2") (pintype "passive"))
    )
    (net (code "67") (name "Net-(U10-X2)") (class "Default")
      (node (ref "C8") (pin "1") (pinfunction "1_1") (pintype "passive"))
      (node (ref "U10") (pin "8") (pinfunction "X2_8") (pintype "output"))
      (node (ref "Y1") (pin "1") (pinfunction "OSC1_1") (pintype "passive"))
    )
    (net (code "68") (name "Net-(U11-V_OUT)") (class "Default")
      (node (ref "U11") (pin "6") (pinfunction "V_OUT_6") (pintype "output"))
      (node (ref "U9") (pin "4") (pinfunction "D_4") (pintype "input"))
    )
    (net (code "69") (name "VCC_ISO") (class "Default")
      (node (ref "C11") (pin "1") (pinfunction "1_1") (pintype "passive"))
      (node (ref "C13") (pin "2") (pinfunction "2_2") (pintype "passive"))
      (node (ref "C15") (pin "2") (pinfunction "2_2") (pintype "passive"))
      (node (ref "C6") (pin "2") (pinfunction "2_2") (pintype "passive"))
      (node (ref "C9") (pin "2") (pinfunction "2_2") (pintype "passive"))
      (node (ref "J1") (pin "6") (pinfunction "6_6") (pintype "passive"))
      (node (ref "R2") (pin "2") (pinfunction "2_2") (pintype "passive"))
      (node (ref "U11") (pin "8") (pinfunction "VDD2_8") (pintype "power_in"))
      (node (ref "U4") (pin "5") (pinfunction "OUT_5") (pintype "power_in"))
      (node (ref "U5") (pin "7") (pinfunction "V_E_7") (pintype "power_in"))
      (node (ref "U5") (pin "8") (pinfunction "VCC_8") (pintype "power_in"))
      (node (ref "U8") (pin "1") (pinfunction "VDD1_1") (pintype "power_in"))
      (node (ref "U9") (pin "8") (pinfunction "VCC_8") (pintype "power_in"))
    )
    (net (code "70") (name "unconnected-(DISP1-DB0-Pad7)") (class "Default")
      (node (ref "DISP1") (pin "7") (pinfunction "DB0_7") (pintype "passive"))
    )
    (net (code "71") (name "unconnected-(DISP1-DB1-Pad8)") (class "Default")
      (node (ref "DISP1") (pin "8") (pinfunction "DB1_8") (pintype "passive"))
    )
    (net (code "72") (name "unconnected-(DISP1-DB2-Pad9)") (class "Default")
      (node (ref "DISP1") (pin "9") (pinfunction "DB2_9") (pintype "passive"))
    )
    (net (code "73") (name "unconnected-(DISP1-DB3-Pad10)") (class "Default")
      (node (ref "DISP1") (pin "10") (pinfunction "DB3_10") (pintype "passive"))
    )
    (net (code "74") (name "unconnected-(J1-MH1-Pad10)") (class "Default")
      (node (ref "J1") (pin "10") (pinfunction "MH1_10") (pintype "passive"))
    )
    (net (code "75") (name "unconnected-(J1-MH2-Pad11)") (class "Default")
      (node (ref "J1") (pin "11") (pinfunction "MH2_11") (pintype "passive"))
    )
    (net (code "76") (name "unconnected-(J1-Pad1)") (class "Default")
      (node (ref "J1") (pin "1") (pinfunction "1_1") (pintype "passive+no_connect"))
    )
    (net (code "77") (name "unconnected-(J1-Pad2)") (class "Default")
      (node (ref "J1") (pin "2") (pinfunction "2_2") (pintype "passive+no_connect"))
    )
    (net (code "78") (name "unconnected-(J1-Pad4)") (class "Default")
      (node (ref "J1") (pin "4") (pinfunction "4_4") (pintype "passive"))
    )
    (net (code "79") (name "unconnected-(J1-Pad7)") (class "Default")
      (node (ref "J1") (pin "7") (pinfunction "7_7") (pintype "passive+no_connect"))
    )
    (net (code "80") (name "unconnected-(J1-Pad9)") (class "Default")
      (node (ref "J1") (pin "9") (pinfunction "9_9") (pintype "passive+no_connect"))
    )
    (net (code "81") (name "unconnected-(U3-NC-Pad8)") (class "Default")
      (node (ref "U3") (pin "8") (pinfunction "NC_8") (pintype "passive"))
    )
    (net (code "82") (name "unconnected-(U5-Pad1)") (class "Default")
      (node (ref "U5") (pin "1") (pintype "passive+no_connect"))
    )
    (net (code "83") (name "unconnected-(U5-Pad4)") (class "Default")
      (node (ref "U5") (pin "4") (pintype "passive+no_connect"))
    )
    (net (code "84") (name "unconnected-(U8-Pad3)") (class "Default")
      (node (ref "U8") (pin "3") (pintype "passive+no_connect"))
    )
    (net (code "85") (name "unconnected-(U8-Pad7)") (class "Default")
      (node (ref "U8") (pin "7") (pintype "passive+no_connect"))
    )
    (net (code "86") (name "unconnected-(U10-CMSEL-Pad3)") (class "Default")
      (node (ref "U10") (pin "3") (pinfunction "CMSEL_3") (pintype "input+no_connect"))
    )
    (net (code "87") (name "unconnected-(U11-Pad3)") (class "Default")
      (node (ref "U11") (pin "3") (pintype "passive+no_connect"))
    )
    (net (code "88") (name "unconnected-(U11-Pad7)") (class "Default")
      (node (ref "U11") (pin "7") (pintype "passive+no_connect"))
    )
    (net (code "89") (name "unconnected-(U12-PA8-Pad29)") (class "Default")
      (node (ref "U12") (pin "29") (pinfunction "PA8_29") (pintype "bidirectional"))
    )
    (net (code "90") (name "unconnected-(U12-PB0-Pad18)") (class "Default")
      (node (ref "U12") (pin "18") (pinfunction "PB0_18") (pintype "bidirectional"))
    )
    (net (code "91") (name "unconnected-(U12-PB15-Pad28)") (class "Default")
      (node (ref "U12") (pin "28") (pinfunction "PB15_28") (pintype "bidirectional"))
    )
    (net (code "92") (name "unconnected-(U12-PC13-TAMPER-RTC-Pad2)") (class "Default")
      (node (ref "U12") (pin "2") (pinfunction "PC13-TAMPER-RTC_2") (pintype "bidirectional"))
    )
  )
)
